# EMG.net
KiCad netlist of a schematic drawn in Altium Designer
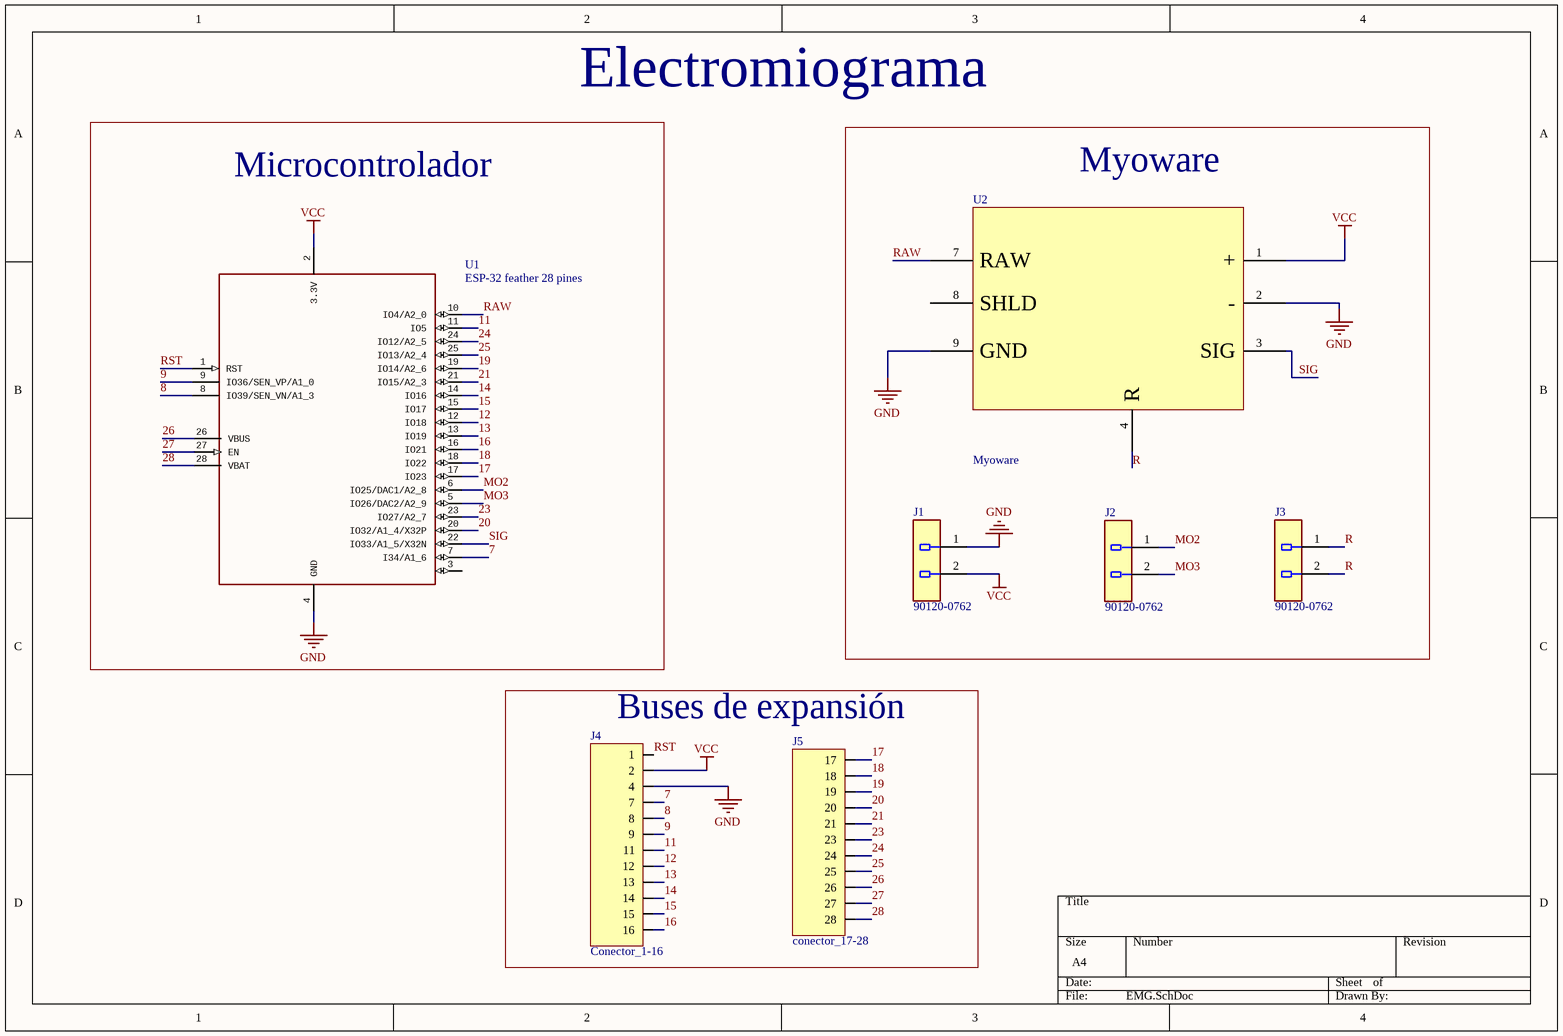
[diagram p0: EMG.SchDoc]

(export (version "E")
  (design (tool "Eeschema 10.0.6"))
  (components
    (comp (ref "J1")
      (value "Conn_Molex_90120-0762_eec")
      (footprint "Molex_90120-0762_0")
      (description "CONN HEADER 2POS .100\" STR GOLD")
      (fields
        (field (name "MANUFACTURER") "Molex")
        (field (name "MOUSER PART NUMBER") "538-90120-0762")
        (field (name "PART NUMBER") "90120-0762")
      )
      (libsource (lib "SnapEDA_Library") (part "Conn_Molex_90120-0762_eec"))
    )
    (comp (ref "J2")
      (value "Conn_Molex_90120-0762_eec")
      (footprint "Molex_90120-0762_0")
      (description "CONN HEADER 2POS .100\" STR GOLD")
      (fields
        (field (name "MANUFACTURER") "Molex")
        (field (name "MOUSER PART NUMBER") "538-90120-0762")
        (field (name "PART NUMBER") "90120-0762")
      )
      (libsource (lib "SnapEDA_Library") (part "Conn_Molex_90120-0762_eec"))
    )
    (comp (ref "J3")
      (value "Conn_Molex_90120-0762_eec")
      (footprint "Molex_90120-0762_0")
      (description "CONN HEADER 2POS .100\" STR GOLD")
      (fields
        (field (name "MANUFACTURER") "Molex")
        (field (name "MOUSER PART NUMBER") "538-90120-0762")
        (field (name "PART NUMBER") "90120-0762")
      )
      (libsource (lib "SnapEDA_Library") (part "Conn_Molex_90120-0762_eec"))
    )
    (comp (ref "J4")
      (value "Conector_1-16")
      (footprint "pines_1-16:PCBComponent_1")
      (libsource (lib "pines_1-16") (part "Conector_1-16"))
    )
    (comp (ref "J5")
      (value "conector_17-28")
      (footprint "pines_17-28:PCBComponent_1")
      (libsource (lib "pines_17-28") (part "conector_17-28"))
    )
    (comp (ref "U1")
      (value "ESP-32 feather 28 pines")
      (footprint "ESP32-Feather-footprint_v3")
      (libsource (lib "SnapEDA_Library") (part "ESP32-Feather"))
    )
    (comp (ref "U2")
      (value "Myoware")
      (footprint "Myoware_footprint_v4")
      (libsource (lib "Myoware") (part "Myoware"))
    )
  )
  (nets
    (net (code "1") (name "/7") (class "Default")
      (node (ref "J4") (pin "7") (pinfunction "7_7") (pintype "passive"))
      (node (ref "U1") (pin "7") (pinfunction "I34/A1_6_7") (pintype "bidirectional"))
    )
    (net (code "2") (name "/8") (class "Default")
      (node (ref "J4") (pin "8") (pinfunction "8_8") (pintype "passive"))
      (node (ref "U1") (pin "8") (pinfunction "IO39/SEN_VN/A1_3_8") (pintype "passive"))
    )
    (net (code "3") (name "/9") (class "Default")
      (node (ref "J4") (pin "9") (pinfunction "9_9") (pintype "passive"))
      (node (ref "U1") (pin "9") (pinfunction "IO36/SEN_VP/A1_0_9") (pintype "passive"))
    )
    (net (code "4") (name "/11") (class "Default")
      (node (ref "J4") (pin "11") (pinfunction "11_11") (pintype "passive"))
      (node (ref "U1") (pin "11") (pinfunction "IO5_11") (pintype "bidirectional"))
    )
    (net (code "5") (name "/12") (class "Default")
      (node (ref "J4") (pin "12") (pinfunction "12_12") (pintype "passive"))
      (node (ref "U1") (pin "12") (pinfunction "IO18_12") (pintype "bidirectional"))
    )
    (net (code "6") (name "/13") (class "Default")
      (node (ref "J4") (pin "13") (pinfunction "13_13") (pintype "passive"))
      (node (ref "U1") (pin "13") (pinfunction "IO19_13") (pintype "bidirectional"))
    )
    (net (code "7") (name "/14") (class "Default")
      (node (ref "J4") (pin "14") (pinfunction "14_14") (pintype "passive"))
      (node (ref "U1") (pin "14") (pinfunction "IO16_14") (pintype "bidirectional"))
    )
    (net (code "8") (name "/15") (class "Default")
      (node (ref "J4") (pin "15") (pinfunction "15_15") (pintype "passive"))
      (node (ref "U1") (pin "15") (pinfunction "IO17_15") (pintype "bidirectional"))
    )
    (net (code "9") (name "/16") (class "Default")
      (node (ref "J4") (pin "16") (pinfunction "16_16") (pintype "passive"))
      (node (ref "U1") (pin "16") (pinfunction "IO21_16") (pintype "bidirectional"))
    )
    (net (code "10") (name "/17") (class "Default")
      (node (ref "J5") (pin "17") (pinfunction "17_17") (pintype "passive"))
      (node (ref "U1") (pin "17") (pinfunction "IO23_17") (pintype "bidirectional"))
    )
    (net (code "11") (name "/18") (class "Default")
      (node (ref "J5") (pin "18") (pinfunction "18_18") (pintype "passive"))
      (node (ref "U1") (pin "18") (pinfunction "IO22_18") (pintype "bidirectional"))
    )
    (net (code "12") (name "/19") (class "Default")
      (node (ref "J5") (pin "19") (pinfunction "19_19") (pintype "passive"))
      (node (ref "U1") (pin "19") (pinfunction "IO14/A2_6_19") (pintype "bidirectional"))
    )
    (net (code "13") (name "/20") (class "Default")
      (node (ref "J5") (pin "20") (pinfunction "20_20") (pintype "passive"))
      (node (ref "U1") (pin "20") (pinfunction "IO32/A1_4/X32P_20") (pintype "bidirectional"))
    )
    (net (code "14") (name "/21") (class "Default")
      (node (ref "J5") (pin "21") (pinfunction "21_21") (pintype "passive"))
      (node (ref "U1") (pin "21") (pinfunction "IO15/A2_3_21") (pintype "bidirectional"))
    )
    (net (code "15") (name "/23") (class "Default")
      (node (ref "J5") (pin "23") (pinfunction "23_23") (pintype "passive"))
      (node (ref "U1") (pin "23") (pinfunction "IO27/A2_7_23") (pintype "bidirectional"))
    )
    (net (code "16") (name "/24") (class "Default")
      (node (ref "J5") (pin "24") (pinfunction "24_24") (pintype "passive"))
      (node (ref "U1") (pin "24") (pinfunction "IO12/A2_5_24") (pintype "bidirectional"))
    )
    (net (code "17") (name "/25") (class "Default")
      (node (ref "J5") (pin "25") (pinfunction "25_25") (pintype "passive"))
      (node (ref "U1") (pin "25") (pinfunction "IO13/A2_4_25") (pintype "bidirectional"))
    )
    (net (code "18") (name "/26") (class "Default")
      (node (ref "J5") (pin "26") (pinfunction "26_26") (pintype "passive"))
      (node (ref "U1") (pin "26") (pinfunction "VBUS_26") (pintype "power_in"))
    )
    (net (code "19") (name "/27") (class "Default")
      (node (ref "J5") (pin "27") (pinfunction "27_27") (pintype "passive"))
      (node (ref "U1") (pin "27") (pinfunction "EN_27") (pintype "input"))
    )
    (net (code "20") (name "/28") (class "Default")
      (node (ref "J5") (pin "28") (pinfunction "28_28") (pintype "passive"))
      (node (ref "U1") (pin "28") (pinfunction "VBAT_28") (pintype "power_in"))
    )
    (net (code "21") (name "/MO2") (class "Default")
      (node (ref "J2") (pin "1") (pinfunction "1_1") (pintype "passive"))
      (node (ref "U1") (pin "6") (pinfunction "IO25/DAC1/A2_8_6") (pintype "bidirectional"))
    )
    (net (code "22") (name "/MO3") (class "Default")
      (node (ref "J2") (pin "2") (pinfunction "2_2") (pintype "passive"))
      (node (ref "U1") (pin "5") (pinfunction "IO26/DAC2/A2_9_5") (pintype "bidirectional"))
    )
    (net (code "23") (name "/R") (class "Default")
      (node (ref "J3") (pin "1") (pinfunction "1_1") (pintype "passive"))
      (node (ref "J3") (pin "2") (pinfunction "2_2") (pintype "passive"))
      (node (ref "U2") (pin "4") (pinfunction "R_4") (pintype "passive"))
    )
    (net (code "24") (name "/RAW") (class "Default")
      (node (ref "U1") (pin "10") (pinfunction "IO4/A2_0_10") (pintype "bidirectional"))
      (node (ref "U2") (pin "7") (pinfunction "RAW_7") (pintype "passive"))
    )
    (net (code "25") (name "/RST") (class "Default")
      (node (ref "J4") (pin "1") (pinfunction "1_1") (pintype "passive"))
      (node (ref "U1") (pin "1") (pinfunction "RST_1") (pintype "input"))
    )
    (net (code "26") (name "/SIG") (class "Default")
      (node (ref "U1") (pin "22") (pinfunction "IO33/A1_5/X32N_22") (pintype "bidirectional"))
      (node (ref "U2") (pin "3") (pinfunction "SIG_3") (pintype "passive"))
    )
    (net (code "27") (name "GND") (class "Default")
      (node (ref "J1") (pin "1") (pinfunction "1_1") (pintype "passive"))
      (node (ref "J4") (pin "4") (pinfunction "4_4") (pintype "passive"))
      (node (ref "U1") (pin "4") (pinfunction "GND_4") (pintype "passive"))
      (node (ref "U2") (pin "2") (pinfunction "-_2") (pintype "passive"))
      (node (ref "U2") (pin "9") (pinfunction "GND_9") (pintype "passive"))
    )
    (net (code "28") (name "VCC") (class "Default")
      (node (ref "J1") (pin "2") (pinfunction "2_2") (pintype "passive"))
      (node (ref "J4") (pin "2") (pinfunction "2_2") (pintype "passive"))
      (node (ref "U1") (pin "2") (pinfunction "3.3V_2") (pintype "passive"))
      (node (ref "U2") (pin "1") (pinfunction "+_1") (pintype "passive"))
    )
    (net (code "29") (name "unconnected-(U1-Pad3)") (class "Default")
      (node (ref "U1") (pin "3") (pintype "bidirectional"))
    )
    (net (code "30") (name "unconnected-(U2-SHLD-Pad8)") (class "Default")
      (node (ref "U2") (pin "8") (pinfunction "SHLD_8") (pintype "passive"))
    )
  )
)
